# Sheet1.net
KiCad netlist of a schematic drawn in Altium Designer
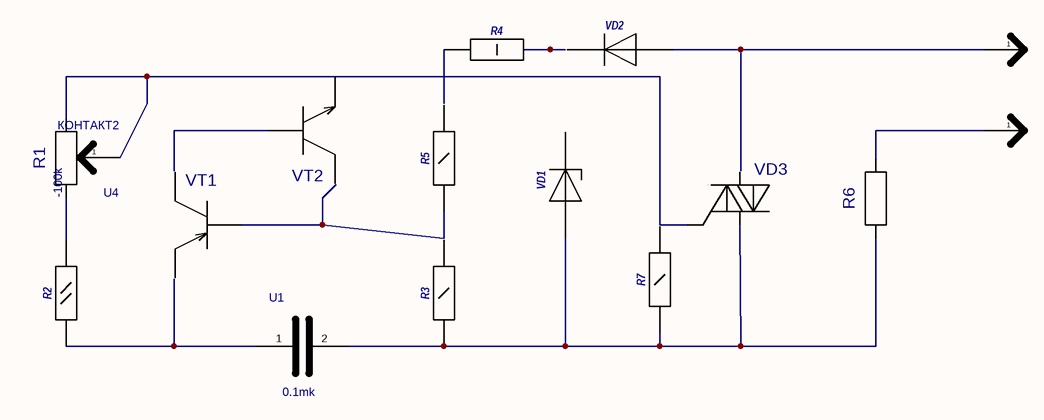
[diagram p0: Sheet1.SCHDOC]

(export (version "E")
  (design (tool "Eeschema 10.0.6"))
  (components
    (comp (ref "R1") (value "-100k") (footprint "R1W") (description "R1W") (libsource (lib "*") (part "R1W")))
    (comp (ref "R2") (value "МЛТ(0.125)") (footprint "МЛТ(0.125)") (libsource (lib "*") (part "МЛТ(0.125)")))
    (comp (ref "R3") (value "МЛТ(0.25)") (footprint "МЛТ(0.25)") (libsource (lib "*") (part "МЛТ(0.25)")))
    (comp (ref "R4") (value "МЛТ(1)") (footprint "МЛТ(1)") (libsource (lib "*") (part "МЛТ(1)")))
    (comp (ref "R5") (value "МЛТ(0.25)") (footprint "МЛТ(0.25)") (libsource (lib "*") (part "МЛТ(0.25)")))
    (comp (ref "R6")
      (value "R1W")
      (footprint "R1W")
      (description "R1W_VARIANT_1")
      (libsource (lib "*") (part "R1W"))
    )
    (comp (ref "R7") (value "МЛТ(0.25)") (footprint "МЛТ(0.25)") (libsource (lib "*") (part "МЛТ(0.25)")))
    (comp (ref "U") (value "КОНТАКТ2") (libsource (lib "*") (part "КОНТАКТ2")))
    (comp (ref "U1") (value "0.1mk") (description "K50-29") (libsource (lib "*") (part "K50-29")))
    (comp (ref "U2")
      (value "КОНТАКТ2")
      (description "КОНТАКТ2_VARIANT_1")
      (libsource (lib "*") (part "КОНТАКТ2"))
    )
    (comp (ref "U4")
      (value "КОНТАКТ2")
      (description "КОНТАКТ2_VARIANT_1")
      (libsource (lib "*") (part "КОНТАКТ2"))
    )
    (comp (ref "VD1") (value "KC139A") (footprint "KC139") (libsource (lib "*") (part "KC139A")))
    (comp (ref "VD2") (value "КД522Б") (footprint "КД522") (libsource (lib "*") (part "КД522Б")))
    (comp (ref "VD3") (value "KU605") (footprint "KT28-1") (libsource (lib "*") (part "KU605")))
    (comp (ref "VT1") (value "KT361") (footprint "KT13") (libsource (lib "*") (part "KT361")))
    (comp (ref "VT2") (value "KT315") (footprint "KT13") (libsource (lib "*") (part "KT315")))
  )
  (nets
    (net (code "1") (name "Net-(R1-I{slash}OA)") (class "Default")
      (node (ref "R1") (pin "1") (pinfunction "I/OA_1") (pintype "passive"))
      (node (ref "R2") (pin "2") (pinfunction "2_2") (pintype "passive"))
    )
    (net (code "2") (name "Net-(R1-I{slash}OB)") (class "Default")
      (node (ref "R1") (pin "2") (pinfunction "I/OB_2") (pintype "passive"))
      (node (ref "U4") (pin "1") (pintype "passive"))
      (node (ref "VD3") (pin "2") (pinfunction "I/OB_2") (pintype "passive"))
    )
    (net (code "3") (name "Net-(R2-Pad1)") (class "Default")
      (node (ref "R2") (pin "1") (pinfunction "1_1") (pintype "passive"))
      (node (ref "U1") (pin "1") (pintype "passive"))
    )
    (net (code "4") (name "Net-(R6-I{slash}OA)") (class "Default")
      (node (ref "R3") (pin "1") (pinfunction "1_1") (pintype "passive"))
      (node (ref "R6") (pin "1") (pinfunction "I/OA_1") (pintype "passive"))
      (node (ref "R7") (pin "1") (pinfunction "1_1") (pintype "passive"))
      (node (ref "U1") (pin "2") (pintype "passive"))
      (node (ref "VD1") (pin "1") (pinfunction "1_1") (pintype "passive"))
      (node (ref "VD3") (pin "3") (pinfunction "IN_3") (pintype "passive"))
    )
    (net (code "5") (name "Net-(R6-I{slash}OB)") (class "Default")
      (node (ref "R6") (pin "2") (pinfunction "I/OB_2") (pintype "passive"))
      (node (ref "U") (pin "1") (pintype "passive"))
    )
    (net (code "6") (name "Net-(U2-Pad1)") (class "Default")
      (node (ref "U2") (pin "1") (pintype "passive"))
      (node (ref "VD2") (pin "1") (pinfunction "1_1") (pintype "passive"))
    )
    (net (code "7") (name "Net-(VT1-B)") (class "Default")
      (node (ref "R5") (pin "1") (pinfunction "1_1") (pintype "passive"))
      (node (ref "VT1") (pin "2") (pinfunction "B_2") (pintype "passive"))
    )
    (net (code "8") (name "unconnected-(R3-Pad2)") (class "Default")
      (node (ref "R3") (pin "2") (pinfunction "2_2") (pintype "passive"))
    )
    (net (code "9") (name "unconnected-(R4-Pad1)") (class "Default")
      (node (ref "R4") (pin "1") (pinfunction "1_1") (pintype "passive"))
    )
    (net (code "10") (name "unconnected-(R4-Pad2)") (class "Default")
      (node (ref "R4") (pin "2") (pinfunction "2_2") (pintype "passive"))
    )
    (net (code "11") (name "unconnected-(R5-Pad2)") (class "Default")
      (node (ref "R5") (pin "2") (pinfunction "2_2") (pintype "passive"))
    )
    (net (code "12") (name "unconnected-(R7-Pad2)") (class "Default")
      (node (ref "R7") (pin "2") (pinfunction "2_2") (pintype "passive"))
    )
    (net (code "13") (name "unconnected-(VD1-Pad2)") (class "Default")
      (node (ref "VD1") (pin "2") (pinfunction "2_2") (pintype "passive"))
    )
    (net (code "14") (name "unconnected-(VD2-Pad2)") (class "Default")
      (node (ref "VD2") (pin "2") (pinfunction "2_2") (pintype "passive"))
    )
    (net (code "15") (name "unconnected-(VD3-I{slash}OA-Pad1)") (class "Default")
      (node (ref "VD3") (pin "1") (pinfunction "I/OA_1") (pintype "passive"))
    )
    (net (code "16") (name "unconnected-(VT1-E-Pad1)") (class "Default")
      (node (ref "VT1") (pin "1") (pinfunction "E_1") (pintype "passive"))
    )
    (net (code "17") (name "unconnected-(VT1-K-Pad3)") (class "Default")
      (node (ref "VT1") (pin "3") (pinfunction "K_3") (pintype "passive"))
    )
    (net (code "18") (name "unconnected-(VT2-B-Pad2)") (class "Default")
      (node (ref "VT2") (pin "2") (pinfunction "B_2") (pintype "passive"))
    )
    (net (code "19") (name "unconnected-(VT2-E-Pad1)") (class "Default")
      (node (ref "VT2") (pin "1") (pinfunction "E_1") (pintype "passive"))
    )
    (net (code "20") (name "unconnected-(VT2-K-Pad3)") (class "Default")
      (node (ref "VT2") (pin "3") (pinfunction "K_3") (pintype "passive"))
    )
  )
)
